# PLCArduinoV1.net
KiCad netlist of a schematic drawn in EAGLE
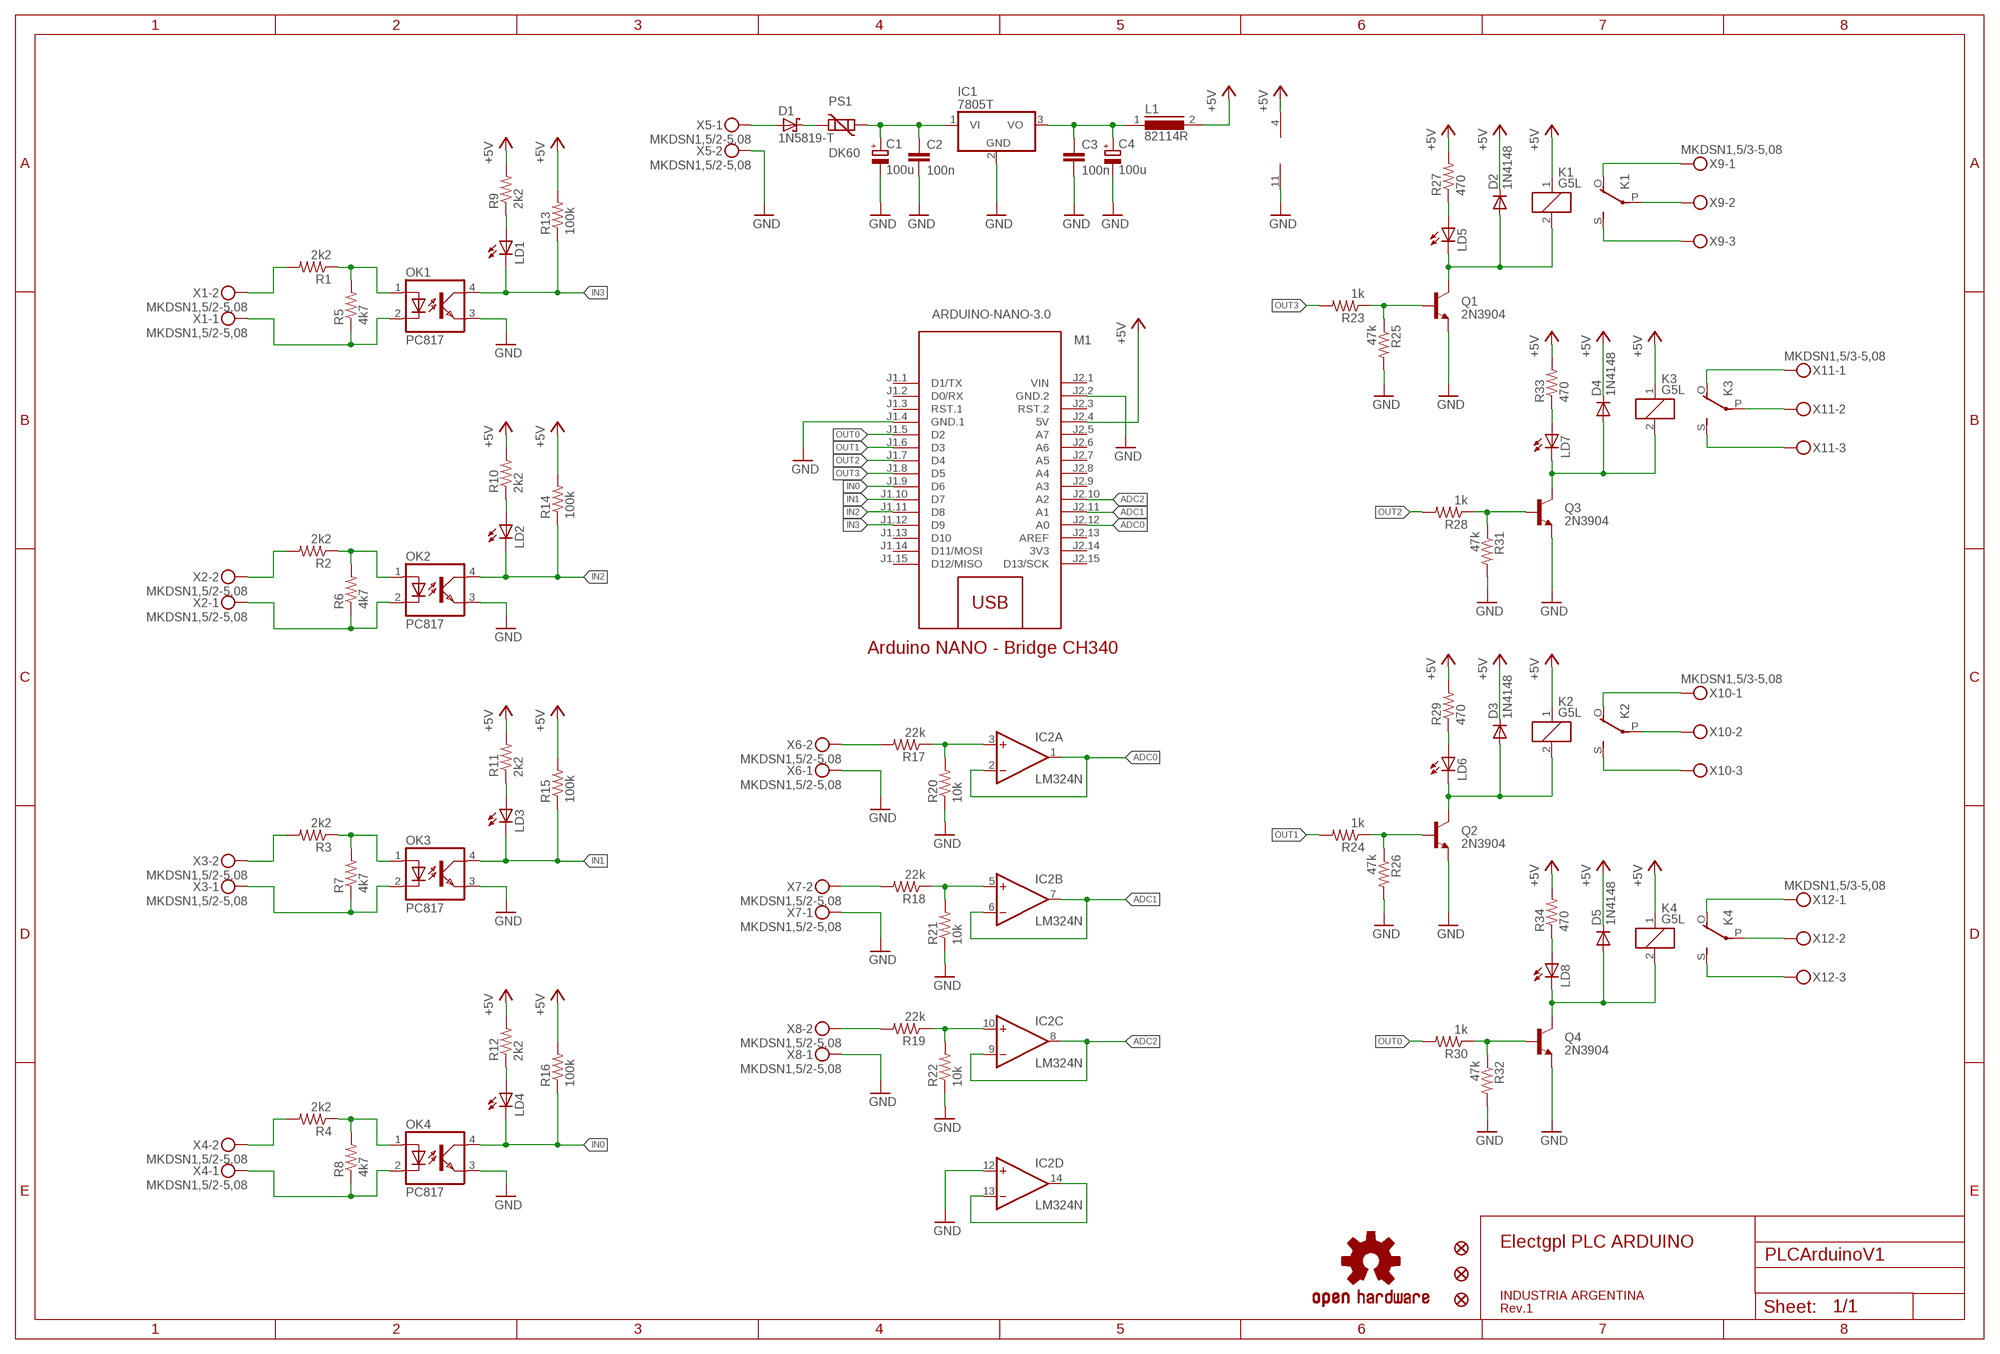
[diagram p0: schematic, sheet 1]

(export (version "E")
  (design (tool "Eeschema 10.0.6"))
  (components
    (comp (ref "C1")
      (value "100u")
      (footprint "eagle-import:E3,5-8")
      (libsource (lib "eagle-import") (part "CPOL-EUE3.5-8"))
    )
    (comp (ref "C2")
      (value "100n")
      (footprint "eagle-import:C050-024X044")
      (libsource (lib "eagle-import") (part "C-EU050-024X044"))
    )
    (comp (ref "C3")
      (value "100n")
      (footprint "eagle-import:C050-024X044")
      (libsource (lib "eagle-import") (part "C-EU050-024X044"))
    )
    (comp (ref "C4")
      (value "100u")
      (footprint "eagle-import:E3,5-8")
      (libsource (lib "eagle-import") (part "CPOL-EUE3.5-8"))
    )
    (comp (ref "D1")
      (value "1N5819-T")
      (footprint "eagle-import:DO41-7.6")
      (libsource (lib "eagle-import") (part "1N5819-T"))
    )
    (comp (ref "D2")
      (value "1N4148")
      (footprint "eagle-import:DO35-10")
      (libsource (lib "eagle-import") (part "1N4148"))
    )
    (comp (ref "D3")
      (value "1N4148")
      (footprint "eagle-import:DO35-10")
      (libsource (lib "eagle-import") (part "1N4148"))
    )
    (comp (ref "D4")
      (value "1N4148")
      (footprint "eagle-import:DO35-10")
      (libsource (lib "eagle-import") (part "1N4148"))
    )
    (comp (ref "D5")
      (value "1N4148")
      (footprint "eagle-import:DO35-10")
      (libsource (lib "eagle-import") (part "1N4148"))
    )
    (comp (ref "IC1")
      (value "7805T")
      (footprint "eagle-import:TO220H")
      (libsource (lib "eagle-import") (part "78T05"))
    )
    (comp (ref "IC2")
      (value "LM324N")
      (footprint "eagle-import:DIL14")
      (libsource (lib "eagle-import") (part "LM324N"))
    )
    (comp (ref "JP1")
      (value "FIDUCIAL1X2.5")
      (footprint "eagle-import:FIDUCIAL-1X2.5")
      (libsource (lib "eagle-import") (part "FIDUCIAL1X2.5"))
    )
    (comp (ref "JP2")
      (value "FIDUCIAL1X2.5")
      (footprint "eagle-import:FIDUCIAL-1X2.5")
      (libsource (lib "eagle-import") (part "FIDUCIAL1X2.5"))
    )
    (comp (ref "JP3")
      (value "FIDUCIAL1X2.5")
      (footprint "eagle-import:FIDUCIAL-1X2.5")
      (libsource (lib "eagle-import") (part "FIDUCIAL1X2.5"))
    )
    (comp (ref "K1")
      (value "G5L")
      (footprint "eagle-import:G5LE")
      (libsource (lib "eagle-import") (part "G5L"))
    )
    (comp (ref "K2")
      (value "G5L")
      (footprint "eagle-import:G5LE")
      (libsource (lib "eagle-import") (part "G5L"))
    )
    (comp (ref "K3")
      (value "G5L")
      (footprint "eagle-import:G5LE")
      (libsource (lib "eagle-import") (part "G5L"))
    )
    (comp (ref "K4")
      (value "G5L")
      (footprint "eagle-import:G5LE")
      (libsource (lib "eagle-import") (part "G5L"))
    )
    (comp (ref "L1")
      (value "82114R")
      (footprint "eagle-import:82114R")
      (libsource (lib "eagle-import") (part "82114R"))
    )
    (comp (ref "LD1")
      (value "LED3MM")
      (footprint "eagle-import:LED3MM")
      (libsource (lib "eagle-import") (part "LED3MM"))
    )
    (comp (ref "LD2")
      (value "LED3MM")
      (footprint "eagle-import:LED3MM")
      (libsource (lib "eagle-import") (part "LED3MM"))
    )
    (comp (ref "LD3")
      (value "LED3MM")
      (footprint "eagle-import:LED3MM")
      (libsource (lib "eagle-import") (part "LED3MM"))
    )
    (comp (ref "LD4")
      (value "LED3MM")
      (footprint "eagle-import:LED3MM")
      (libsource (lib "eagle-import") (part "LED3MM"))
    )
    (comp (ref "LD5")
      (value "LED3MM")
      (footprint "eagle-import:LED3MM")
      (libsource (lib "eagle-import") (part "LED3MM"))
    )
    (comp (ref "LD6")
      (value "LED3MM")
      (footprint "eagle-import:LED3MM")
      (libsource (lib "eagle-import") (part "LED3MM"))
    )
    (comp (ref "LD7")
      (value "LED3MM")
      (footprint "eagle-import:LED3MM")
      (libsource (lib "eagle-import") (part "LED3MM"))
    )
    (comp (ref "LD8")
      (value "LED3MM")
      (footprint "eagle-import:LED3MM")
      (libsource (lib "eagle-import") (part "LED3MM"))
    )
    (comp (ref "M1")
      (value "ARDUINO-NANO-3.0")
      (footprint "eagle-import:ARDUINO-NANO-3.0")
      (libsource (lib "eagle-import") (part "ARDUINO-NANO-3.0"))
    )
    (comp (ref "OK1")
      (value "PC817")
      (footprint "eagle-import:DIL04")
      (libsource (lib "eagle-import") (part "PC817"))
    )
    (comp (ref "OK2")
      (value "PC817")
      (footprint "eagle-import:DIL04")
      (libsource (lib "eagle-import") (part "PC817"))
    )
    (comp (ref "OK3")
      (value "PC817")
      (footprint "eagle-import:DIL04")
      (libsource (lib "eagle-import") (part "PC817"))
    )
    (comp (ref "OK4")
      (value "PC817")
      (footprint "eagle-import:DIL04")
      (libsource (lib "eagle-import") (part "PC817"))
    )
    (comp (ref "PS1")
      (value "DK60")
      (footprint "eagle-import:SO5K11")
      (libsource (lib "eagle-import") (part "POLYSWITCH5MM"))
    )
    (comp (ref "Q1")
      (value "2N3904")
      (footprint "eagle-import:TO92")
      (libsource (lib "eagle-import") (part "2N3904"))
    )
    (comp (ref "Q2")
      (value "2N3904")
      (footprint "eagle-import:TO92")
      (libsource (lib "eagle-import") (part "2N3904"))
    )
    (comp (ref "Q3")
      (value "2N3904")
      (footprint "eagle-import:TO92")
      (libsource (lib "eagle-import") (part "2N3904"))
    )
    (comp (ref "Q4")
      (value "2N3904")
      (footprint "eagle-import:TO92")
      (libsource (lib "eagle-import") (part "2N3904"))
    )
    (comp (ref "R1")
      (value "2k2")
      (footprint "eagle-import:0204_5")
      (libsource (lib "eagle-import") (part "R-US_0204/5"))
    )
    (comp (ref "R2")
      (value "2k2")
      (footprint "eagle-import:0204_5")
      (libsource (lib "eagle-import") (part "R-US_0204/5"))
    )
    (comp (ref "R3")
      (value "2k2")
      (footprint "eagle-import:0204_5")
      (libsource (lib "eagle-import") (part "R-US_0204/5"))
    )
    (comp (ref "R4")
      (value "2k2")
      (footprint "eagle-import:0204_5")
      (libsource (lib "eagle-import") (part "R-US_0204/5"))
    )
    (comp (ref "R5")
      (value "4k7")
      (footprint "eagle-import:0204_5")
      (libsource (lib "eagle-import") (part "R-US_0204/5"))
    )
    (comp (ref "R6")
      (value "4k7")
      (footprint "eagle-import:0204_5")
      (libsource (lib "eagle-import") (part "R-US_0204/5"))
    )
    (comp (ref "R7")
      (value "4k7")
      (footprint "eagle-import:0204_5")
      (libsource (lib "eagle-import") (part "R-US_0204/5"))
    )
    (comp (ref "R8")
      (value "4k7")
      (footprint "eagle-import:0204_5")
      (libsource (lib "eagle-import") (part "R-US_0204/5"))
    )
    (comp (ref "R9")
      (value "2k2")
      (footprint "eagle-import:0204_5")
      (libsource (lib "eagle-import") (part "R-US_0204/5"))
    )
    (comp (ref "R10")
      (value "2k2")
      (footprint "eagle-import:0204_5")
      (libsource (lib "eagle-import") (part "R-US_0204/5"))
    )
    (comp (ref "R11")
      (value "2k2")
      (footprint "eagle-import:0204_5")
      (libsource (lib "eagle-import") (part "R-US_0204/5"))
    )
    (comp (ref "R12")
      (value "2k2")
      (footprint "eagle-import:0204_5")
      (libsource (lib "eagle-import") (part "R-US_0204/5"))
    )
    (comp (ref "R13")
      (value "100k")
      (footprint "eagle-import:0204_5")
      (libsource (lib "eagle-import") (part "R-US_0204/5"))
    )
    (comp (ref "R14")
      (value "100k")
      (footprint "eagle-import:0204_5")
      (libsource (lib "eagle-import") (part "R-US_0204/5"))
    )
    (comp (ref "R15")
      (value "100k")
      (footprint "eagle-import:0204_5")
      (libsource (lib "eagle-import") (part "R-US_0204/5"))
    )
    (comp (ref "R16")
      (value "100k")
      (footprint "eagle-import:0204_5")
      (libsource (lib "eagle-import") (part "R-US_0204/5"))
    )
    (comp (ref "R17")
      (value "22k")
      (footprint "eagle-import:0204_5")
      (libsource (lib "eagle-import") (part "R-US_0204/5"))
    )
    (comp (ref "R18")
      (value "22k")
      (footprint "eagle-import:0204_5")
      (libsource (lib "eagle-import") (part "R-US_0204/5"))
    )
    (comp (ref "R19")
      (value "22k")
      (footprint "eagle-import:0204_5")
      (libsource (lib "eagle-import") (part "R-US_0204/5"))
    )
    (comp (ref "R20")
      (value "10k")
      (footprint "eagle-import:0204_5")
      (libsource (lib "eagle-import") (part "R-US_0204/5"))
    )
    (comp (ref "R21")
      (value "10k")
      (footprint "eagle-import:0204_5")
      (libsource (lib "eagle-import") (part "R-US_0204/5"))
    )
    (comp (ref "R22")
      (value "10k")
      (footprint "eagle-import:0204_5")
      (libsource (lib "eagle-import") (part "R-US_0204/5"))
    )
    (comp (ref "R23")
      (value "1k")
      (footprint "eagle-import:0204_5")
      (libsource (lib "eagle-import") (part "R-US_0204/5"))
    )
    (comp (ref "R24")
      (value "1k")
      (footprint "eagle-import:0204_5")
      (libsource (lib "eagle-import") (part "R-US_0204/5"))
    )
    (comp (ref "R25")
      (value "47k")
      (footprint "eagle-import:0204_5")
      (libsource (lib "eagle-import") (part "R-US_0204/5"))
    )
    (comp (ref "R26")
      (value "47k")
      (footprint "eagle-import:0204_5")
      (libsource (lib "eagle-import") (part "R-US_0204/5"))
    )
    (comp (ref "R27")
      (value "470")
      (footprint "eagle-import:0204_5")
      (libsource (lib "eagle-import") (part "R-US_0204/5"))
    )
    (comp (ref "R28")
      (value "1k")
      (footprint "eagle-import:0204_5")
      (libsource (lib "eagle-import") (part "R-US_0204/5"))
    )
    (comp (ref "R29")
      (value "470")
      (footprint "eagle-import:0204_5")
      (libsource (lib "eagle-import") (part "R-US_0204/5"))
    )
    (comp (ref "R30")
      (value "1k")
      (footprint "eagle-import:0204_5")
      (libsource (lib "eagle-import") (part "R-US_0204/5"))
    )
    (comp (ref "R31")
      (value "47k")
      (footprint "eagle-import:0204_5")
      (libsource (lib "eagle-import") (part "R-US_0204/5"))
    )
    (comp (ref "R32")
      (value "47k")
      (footprint "eagle-import:0204_5")
      (libsource (lib "eagle-import") (part "R-US_0204/5"))
    )
    (comp (ref "R33")
      (value "470")
      (footprint "eagle-import:0204_5")
      (libsource (lib "eagle-import") (part "R-US_0204/5"))
    )
    (comp (ref "R34")
      (value "470")
      (footprint "eagle-import:0204_5")
      (libsource (lib "eagle-import") (part "R-US_0204/5"))
    )
    (comp (ref "U1")
      (value "OSHW-LOGOM")
      (footprint "eagle-import:OSHW-LOGO-M")
      (libsource (lib "eagle-import") (part "OSHW-LOGOM"))
    )
    (comp (ref "X1")
      (value "MKDSN1,5/2-5,08")
      (footprint "eagle-import:MKDSN1,5_2-5,08")
      (libsource (lib "eagle-import") (part "MKDSN1,5/2-5,08"))
    )
    (comp (ref "X2")
      (value "MKDSN1,5/2-5,08")
      (footprint "eagle-import:MKDSN1,5_2-5,08")
      (libsource (lib "eagle-import") (part "MKDSN1,5/2-5,08"))
    )
    (comp (ref "X3")
      (value "MKDSN1,5/2-5,08")
      (footprint "eagle-import:MKDSN1,5_2-5,08")
      (libsource (lib "eagle-import") (part "MKDSN1,5/2-5,08"))
    )
    (comp (ref "X4")
      (value "MKDSN1,5/2-5,08")
      (footprint "eagle-import:MKDSN1,5_2-5,08")
      (libsource (lib "eagle-import") (part "MKDSN1,5/2-5,08"))
    )
    (comp (ref "X5")
      (value "MKDSN1,5/2-5,08")
      (footprint "eagle-import:MKDSN1,5_2-5,08")
      (libsource (lib "eagle-import") (part "MKDSN1,5/2-5,08"))
    )
    (comp (ref "X6")
      (value "MKDSN1,5/2-5,08")
      (footprint "eagle-import:MKDSN1,5_2-5,08")
      (libsource (lib "eagle-import") (part "MKDSN1,5/2-5,08"))
    )
    (comp (ref "X7")
      (value "MKDSN1,5/2-5,08")
      (footprint "eagle-import:MKDSN1,5_2-5,08")
      (libsource (lib "eagle-import") (part "MKDSN1,5/2-5,08"))
    )
    (comp (ref "X8")
      (value "MKDSN1,5/2-5,08")
      (footprint "eagle-import:MKDSN1,5_2-5,08")
      (libsource (lib "eagle-import") (part "MKDSN1,5/2-5,08"))
    )
    (comp (ref "X9")
      (value "MKDSN1,5/3-5,08")
      (footprint "eagle-import:MKDSN1,5_3-5,08")
      (libsource (lib "eagle-import") (part "MKDSN1,5/3-5,08"))
    )
    (comp (ref "X10")
      (value "MKDSN1,5/3-5,08")
      (footprint "eagle-import:MKDSN1,5_3-5,08")
      (libsource (lib "eagle-import") (part "MKDSN1,5/3-5,08"))
    )
    (comp (ref "X11")
      (value "MKDSN1,5/3-5,08")
      (footprint "eagle-import:MKDSN1,5_3-5,08")
      (libsource (lib "eagle-import") (part "MKDSN1,5/3-5,08"))
    )
    (comp (ref "X12")
      (value "MKDSN1,5/3-5,08")
      (footprint "eagle-import:MKDSN1,5_3-5,08")
      (libsource (lib "eagle-import") (part "MKDSN1,5/3-5,08"))
    )
  )
  (nets
    (net (code "1") (name "+5V") (class "Default")
      (node (ref "D2") (pin "C") (pinfunction "C_C") (pintype "passive"))
      (node (ref "D3") (pin "C") (pinfunction "C_C") (pintype "passive"))
      (node (ref "D4") (pin "C") (pinfunction "C_C") (pintype "passive"))
      (node (ref "D5") (pin "C") (pinfunction "C_C") (pintype "passive"))
      (node (ref "IC2") (pin "4") (pinfunction "V+_4") (pintype "power_in"))
      (node (ref "K1") (pin "1") (pinfunction "1_1") (pintype "passive"))
      (node (ref "K2") (pin "1") (pinfunction "1_1") (pintype "passive"))
      (node (ref "K3") (pin "1") (pinfunction "1_1") (pintype "passive"))
      (node (ref "K4") (pin "1") (pinfunction "1_1") (pintype "passive"))
      (node (ref "L1") (pin "2") (pinfunction "2_2") (pintype "passive"))
      (node (ref "M1") (pin "J2.4") (pinfunction "5V_J2.4") (pintype "power_in"))
      (node (ref "R10") (pin "2") (pinfunction "2_2") (pintype "passive"))
      (node (ref "R11") (pin "2") (pinfunction "2_2") (pintype "passive"))
      (node (ref "R12") (pin "2") (pinfunction "2_2") (pintype "passive"))
      (node (ref "R13") (pin "2") (pinfunction "2_2") (pintype "passive"))
      (node (ref "R14") (pin "2") (pinfunction "2_2") (pintype "passive"))
      (node (ref "R15") (pin "2") (pinfunction "2_2") (pintype "passive"))
      (node (ref "R16") (pin "2") (pinfunction "2_2") (pintype "passive"))
      (node (ref "R27") (pin "2") (pinfunction "2_2") (pintype "passive"))
      (node (ref "R29") (pin "2") (pinfunction "2_2") (pintype "passive"))
      (node (ref "R33") (pin "2") (pinfunction "2_2") (pintype "passive"))
      (node (ref "R34") (pin "2") (pinfunction "2_2") (pintype "passive"))
      (node (ref "R9") (pin "2") (pinfunction "2_2") (pintype "passive"))
    )
    (net (code "2") (name "/3V3") (class "Default")
      (node (ref "M1") (pin "J2.14") (pinfunction "3V3_J2.14") (pintype "power_in"))
    )
    (net (code "3") (name "/VIN") (class "Default")
      (node (ref "M1") (pin "J2.1") (pinfunction "VIN_J2.1") (pintype "power_in"))
    )
    (net (code "4") (name "ADC0") (class "Default")
      (node (ref "IC2") (pin "1") (pinfunction "OUT_1") (pintype "output"))
      (node (ref "IC2") (pin "2") (pinfunction "-IN_2") (pintype "input"))
      (node (ref "M1") (pin "J2.12") (pinfunction "A0_J2.12") (pintype "bidirectional"))
    )
    (net (code "5") (name "ADC1") (class "Default")
      (node (ref "IC2") (pin "6") (pinfunction "-IN_6") (pintype "input"))
      (node (ref "IC2") (pin "7") (pinfunction "OUT_7") (pintype "output"))
      (node (ref "M1") (pin "J2.11") (pinfunction "A1_J2.11") (pintype "bidirectional"))
    )
    (net (code "6") (name "ADC2") (class "Default")
      (node (ref "IC2") (pin "8") (pinfunction "OUT_8") (pintype "output"))
      (node (ref "IC2") (pin "9") (pinfunction "-IN_9") (pintype "input"))
      (node (ref "M1") (pin "J2.10") (pinfunction "A2_J2.10") (pintype "bidirectional"))
    )
    (net (code "7") (name "GND") (class "Default")
      (node (ref "C1") (pin "-") (pinfunction "-_-") (pintype "passive"))
      (node (ref "C2") (pin "2") (pinfunction "2_2") (pintype "passive"))
      (node (ref "C3") (pin "2") (pinfunction "2_2") (pintype "passive"))
      (node (ref "C4") (pin "-") (pinfunction "-_-") (pintype "passive"))
      (node (ref "IC1") (pin "2") (pinfunction "GND_2") (pintype "passive"))
      (node (ref "IC2") (pin "11") (pinfunction "V-_11") (pintype "power_in"))
      (node (ref "IC2") (pin "12") (pinfunction "+IN_12") (pintype "input"))
      (node (ref "M1") (pin "J1.4") (pinfunction "GND.1_J1.4") (pintype "power_in"))
      (node (ref "M1") (pin "J2.2") (pinfunction "GND.2_J2.2") (pintype "power_in"))
      (node (ref "OK1") (pin "3") (pinfunction "EMIT_3") (pintype "passive"))
      (node (ref "OK2") (pin "3") (pinfunction "EMIT_3") (pintype "passive"))
      (node (ref "OK3") (pin "3") (pinfunction "EMIT_3") (pintype "passive"))
      (node (ref "OK4") (pin "3") (pinfunction "EMIT_3") (pintype "passive"))
      (node (ref "Q1") (pin "3") (pinfunction "E_3") (pintype "passive"))
      (node (ref "Q2") (pin "3") (pinfunction "E_3") (pintype "passive"))
      (node (ref "Q3") (pin "3") (pinfunction "E_3") (pintype "passive"))
      (node (ref "Q4") (pin "3") (pinfunction "E_3") (pintype "passive"))
      (node (ref "R20") (pin "1") (pinfunction "1_1") (pintype "passive"))
      (node (ref "R21") (pin "1") (pinfunction "1_1") (pintype "passive"))
      (node (ref "R22") (pin "1") (pinfunction "1_1") (pintype "passive"))
      (node (ref "R25") (pin "2") (pinfunction "2_2") (pintype "passive"))
      (node (ref "R26") (pin "2") (pinfunction "2_2") (pintype "passive"))
      (node (ref "R31") (pin "2") (pinfunction "2_2") (pintype "passive"))
      (node (ref "R32") (pin "2") (pinfunction "2_2") (pintype "passive"))
      (node (ref "X5") (pin "2") (pinfunction "KL_2") (pintype "passive"))
      (node (ref "X6") (pin "1") (pinfunction "KL_1") (pintype "passive"))
      (node (ref "X7") (pin "1") (pinfunction "KL_1") (pintype "passive"))
      (node (ref "X8") (pin "1") (pinfunction "KL_1") (pintype "passive"))
    )
    (net (code "8") (name "IN0") (class "Default")
      (node (ref "LD4") (pin "K") (pinfunction "C_K") (pintype "passive"))
      (node (ref "M1") (pin "J1.9") (pinfunction "D6_J1.9") (pintype "bidirectional"))
      (node (ref "OK4") (pin "4") (pinfunction "COL_4") (pintype "passive"))
      (node (ref "R16") (pin "1") (pinfunction "1_1") (pintype "passive"))
    )
    (net (code "9") (name "IN1") (class "Default")
      (node (ref "LD3") (pin "K") (pinfunction "C_K") (pintype "passive"))
      (node (ref "M1") (pin "J1.10") (pinfunction "D7_J1.10") (pintype "bidirectional"))
      (node (ref "OK3") (pin "4") (pinfunction "COL_4") (pintype "passive"))
      (node (ref "R15") (pin "1") (pinfunction "1_1") (pintype "passive"))
    )
    (net (code "10") (name "IN2") (class "Default")
      (node (ref "LD2") (pin "K") (pinfunction "C_K") (pintype "passive"))
      (node (ref "M1") (pin "J1.11") (pinfunction "D8_J1.11") (pintype "bidirectional"))
      (node (ref "OK2") (pin "4") (pinfunction "COL_4") (pintype "passive"))
      (node (ref "R14") (pin "1") (pinfunction "1_1") (pintype "passive"))
    )
    (net (code "11") (name "IN3") (class "Default")
      (node (ref "LD1") (pin "K") (pinfunction "C_K") (pintype "passive"))
      (node (ref "M1") (pin "J1.12") (pinfunction "D9_J1.12") (pintype "bidirectional"))
      (node (ref "OK1") (pin "4") (pinfunction "COL_4") (pintype "passive"))
      (node (ref "R13") (pin "1") (pinfunction "1_1") (pintype "passive"))
    )
    (net (code "12") (name "Net-(D1-PadC)") (class "Default")
      (node (ref "D1") (pin "C") (pinfunction "C_C") (pintype "passive"))
      (node (ref "PS1") (pin "2") (pinfunction "2_2") (pintype "passive"))
    )
    (net (code "13") (name "Net-(IC1-VI)") (class "Default")
      (node (ref "C1") (pin "+") (pinfunction "+_+") (pintype "passive"))
      (node (ref "C2") (pin "1") (pinfunction "1_1") (pintype "passive"))
      (node (ref "IC1") (pin "1") (pinfunction "VI_1") (pintype "input"))
      (node (ref "PS1") (pin "1") (pinfunction "1_1") (pintype "passive"))
    )
    (net (code "14") (name "Net-(IC1-VO)") (class "Default")
      (node (ref "C3") (pin "1") (pinfunction "1_1") (pintype "passive"))
      (node (ref "C4") (pin "+") (pinfunction "+_+") (pintype "passive"))
      (node (ref "IC1") (pin "3") (pinfunction "VO_3") (pintype "passive"))
      (node (ref "L1") (pin "1") (pinfunction "1_1") (pintype "passive"))
    )
    (net (code "15") (name "Net-(IC2A-+IN)") (class "Default")
      (node (ref "IC2") (pin "3") (pinfunction "+IN_3") (pintype "input"))
      (node (ref "R17") (pin "1") (pinfunction "1_1") (pintype "passive"))
      (node (ref "R20") (pin "2") (pinfunction "2_2") (pintype "passive"))
    )
    (net (code "16") (name "Net-(IC2B-+IN)") (class "Default")
      (node (ref "IC2") (pin "5") (pinfunction "+IN_5") (pintype "input"))
      (node (ref "R18") (pin "1") (pinfunction "1_1") (pintype "passive"))
      (node (ref "R21") (pin "2") (pinfunction "2_2") (pintype "passive"))
    )
    (net (code "17") (name "Net-(IC2C-+IN)") (class "Default")
      (node (ref "IC2") (pin "10") (pinfunction "+IN_10") (pintype "input"))
      (node (ref "R19") (pin "1") (pinfunction "1_1") (pintype "passive"))
      (node (ref "R22") (pin "2") (pinfunction "2_2") (pintype "passive"))
    )
    (net (code "18") (name "Net-(IC2D--IN)") (class "Default")
      (node (ref "IC2") (pin "13") (pinfunction "-IN_13") (pintype "input"))
      (node (ref "IC2") (pin "14") (pinfunction "OUT_14") (pintype "output"))
    )
    (net (code "19") (name "Net-(LD1-PadA)") (class "Default")
      (node (ref "LD1") (pin "A") (pinfunction "A_A") (pintype "passive"))
      (node (ref "R9") (pin "1") (pinfunction "1_1") (pintype "passive"))
    )
    (net (code "20") (name "Net-(LD2-PadA)") (class "Default")
      (node (ref "LD2") (pin "A") (pinfunction "A_A") (pintype "passive"))
      (node (ref "R10") (pin "1") (pinfunction "1_1") (pintype "passive"))
    )
    (net (code "21") (name "Net-(LD3-PadA)") (class "Default")
      (node (ref "LD3") (pin "A") (pinfunction "A_A") (pintype "passive"))
      (node (ref "R11") (pin "1") (pinfunction "1_1") (pintype "passive"))
    )
    (net (code "22") (name "Net-(LD4-PadA)") (class "Default")
      (node (ref "LD4") (pin "A") (pinfunction "A_A") (pintype "passive"))
      (node (ref "R12") (pin "1") (pinfunction "1_1") (pintype "passive"))
    )
    (net (code "23") (name "Net-(LD5-C)") (class "Default")
      (node (ref "D2") (pin "A") (pinfunction "A_A") (pintype "passive"))
      (node (ref "K1") (pin "2") (pinfunction "2_2") (pintype "passive"))
      (node (ref "LD5") (pin "K") (pinfunction "C_K") (pintype "passive"))
      (node (ref "Q1") (pin "1") (pinfunction "C_1") (pintype "passive"))
    )
    (net (code "24") (name "Net-(LD5-PadA)") (class "Default")
      (node (ref "LD5") (pin "A") (pinfunction "A_A") (pintype "passive"))
      (node (ref "R27") (pin "1") (pinfunction "1_1") (pintype "passive"))
    )
    (net (code "25") (name "Net-(LD6-C)") (class "Default")
      (node (ref "D3") (pin "A") (pinfunction "A_A") (pintype "passive"))
      (node (ref "K2") (pin "2") (pinfunction "2_2") (pintype "passive"))
      (node (ref "LD6") (pin "K") (pinfunction "C_K") (pintype "passive"))
      (node (ref "Q2") (pin "1") (pinfunction "C_1") (pintype "passive"))
    )
    (net (code "26") (name "Net-(LD6-PadA)") (class "Default")
      (node (ref "LD6") (pin "A") (pinfunction "A_A") (pintype "passive"))
      (node (ref "R29") (pin "1") (pinfunction "1_1") (pintype "passive"))
    )
    (net (code "27") (name "Net-(LD7-C)") (class "Default")
      (node (ref "D4") (pin "A") (pinfunction "A_A") (pintype "passive"))
      (node (ref "K3") (pin "2") (pinfunction "2_2") (pintype "passive"))
      (node (ref "LD7") (pin "K") (pinfunction "C_K") (pintype "passive"))
      (node (ref "Q3") (pin "1") (pinfunction "C_1") (pintype "passive"))
    )
    (net (code "28") (name "Net-(LD7-PadA)") (class "Default")
      (node (ref "LD7") (pin "A") (pinfunction "A_A") (pintype "passive"))
      (node (ref "R33") (pin "1") (pinfunction "1_1") (pintype "passive"))
    )
    (net (code "29") (name "Net-(LD8-C)") (class "Default")
      (node (ref "D5") (pin "A") (pinfunction "A_A") (pintype "passive"))
      (node (ref "K4") (pin "2") (pinfunction "2_2") (pintype "passive"))
      (node (ref "LD8") (pin "K") (pinfunction "C_K") (pintype "passive"))
      (node (ref "Q4") (pin "1") (pinfunction "C_1") (pintype "passive"))
    )
    (net (code "30") (name "Net-(LD8-PadA)") (class "Default")
      (node (ref "LD8") (pin "A") (pinfunction "A_A") (pintype "passive"))
      (node (ref "R34") (pin "1") (pinfunction "1_1") (pintype "passive"))
    )
    (net (code "31") (name "Net-(OK1-A)") (class "Default")
      (node (ref "OK1") (pin "1") (pinfunction "A_1") (pintype "passive"))
      (node (ref "R1") (pin "1") (pinfunction "1_1") (pintype "passive"))
      (node (ref "R5") (pin "2") (pinfunction "2_2") (pintype "passive"))
    )
    (net (code "32") (name "Net-(OK1-C)") (class "Default")
      (node (ref "OK1") (pin "2") (pinfunction "C_2") (pintype "passive"))
      (node (ref "R5") (pin "1") (pinfunction "1_1") (pintype "passive"))
      (node (ref "X1") (pin "1") (pinfunction "KL_1") (pintype "passive"))
    )
    (net (code "33") (name "Net-(OK2-A)") (class "Default")
      (node (ref "OK2") (pin "1") (pinfunction "A_1") (pintype "passive"))
      (node (ref "R2") (pin "1") (pinfunction "1_1") (pintype "passive"))
      (node (ref "R6") (pin "2") (pinfunction "2_2") (pintype "passive"))
    )
    (net (code "34") (name "Net-(OK2-C)") (class "Default")
      (node (ref "OK2") (pin "2") (pinfunction "C_2") (pintype "passive"))
      (node (ref "R6") (pin "1") (pinfunction "1_1") (pintype "passive"))
      (node (ref "X2") (pin "1") (pinfunction "KL_1") (pintype "passive"))
    )
    (net (code "35") (name "Net-(OK3-A)") (class "Default")
      (node (ref "OK3") (pin "1") (pinfunction "A_1") (pintype "passive"))
      (node (ref "R3") (pin "1") (pinfunction "1_1") (pintype "passive"))
      (node (ref "R7") (pin "2") (pinfunction "2_2") (pintype "passive"))
    )
    (net (code "36") (name "Net-(OK3-C)") (class "Default")
      (node (ref "OK3") (pin "2") (pinfunction "C_2") (pintype "passive"))
      (node (ref "R7") (pin "1") (pinfunction "1_1") (pintype "passive"))
      (node (ref "X3") (pin "1") (pinfunction "KL_1") (pintype "passive"))
    )
    (net (code "37") (name "Net-(OK4-A)") (class "Default")
      (node (ref "OK4") (pin "1") (pinfunction "A_1") (pintype "passive"))
      (node (ref "R4") (pin "1") (pinfunction "1_1") (pintype "passive"))
      (node (ref "R8") (pin "2") (pinfunction "2_2") (pintype "passive"))
    )
    (net (code "38") (name "Net-(OK4-C)") (class "Default")
      (node (ref "OK4") (pin "2") (pinfunction "C_2") (pintype "passive"))
      (node (ref "R8") (pin "1") (pinfunction "1_1") (pintype "passive"))
      (node (ref "X4") (pin "1") (pinfunction "KL_1") (pintype "passive"))
    )
    (net (code "39") (name "Net-(Q1-B)") (class "Default")
      (node (ref "Q1") (pin "2") (pinfunction "B_2") (pintype "passive"))
      (node (ref "R23") (pin "1") (pinfunction "1_1") (pintype "passive"))
      (node (ref "R25") (pin "1") (pinfunction "1_1") (pintype "passive"))
    )
    (net (code "40") (name "Net-(Q2-B)") (class "Default")
      (node (ref "Q2") (pin "2") (pinfunction "B_2") (pintype "passive"))
      (node (ref "R24") (pin "1") (pinfunction "1_1") (pintype "passive"))
      (node (ref "R26") (pin "1") (pinfunction "1_1") (pintype "passive"))
    )
    (net (code "41") (name "Net-(Q3-B)") (class "Default")
      (node (ref "Q3") (pin "2") (pinfunction "B_2") (pintype "passive"))
      (node (ref "R28") (pin "1") (pinfunction "1_1") (pintype "passive"))
      (node (ref "R31") (pin "1") (pinfunction "1_1") (pintype "passive"))
    )
    (net (code "42") (name "Net-(Q4-B)") (class "Default")
      (node (ref "Q4") (pin "2") (pinfunction "B_2") (pintype "passive"))
      (node (ref "R30") (pin "1") (pinfunction "1_1") (pintype "passive"))
      (node (ref "R32") (pin "1") (pinfunction "1_1") (pintype "passive"))
    )
    (net (code "43") (name "Net-(X1B-KL)") (class "Default")
      (node (ref "R1") (pin "2") (pinfunction "2_2") (pintype "passive"))
      (node (ref "X1") (pin "2") (pinfunction "KL_2") (pintype "passive"))
    )
    (net (code "44") (name "Net-(X2B-KL)") (class "Default")
      (node (ref "R2") (pin "2") (pinfunction "2_2") (pintype "passive"))
      (node (ref "X2") (pin "2") (pinfunction "KL_2") (pintype "passive"))
    )
    (net (code "45") (name "Net-(X3B-KL)") (class "Default")
      (node (ref "R3") (pin "2") (pinfunction "2_2") (pintype "passive"))
      (node (ref "X3") (pin "2") (pinfunction "KL_2") (pintype "passive"))
    )
    (net (code "46") (name "Net-(X4B-KL)") (class "Default")
      (node (ref "R4") (pin "2") (pinfunction "2_2") (pintype "passive"))
      (node (ref "X4") (pin "2") (pinfunction "KL_2") (pintype "passive"))
    )
    (net (code "47") (name "Net-(X5A-KL)") (class "Default")
      (node (ref "D1") (pin "A") (pinfunction "A_A") (pintype "passive"))
      (node (ref "X5") (pin "1") (pinfunction "KL_1") (pintype "passive"))
    )
    (net (code "48") (name "Net-(X6B-KL)") (class "Default")
      (node (ref "R17") (pin "2") (pinfunction "2_2") (pintype "passive"))
      (node (ref "X6") (pin "2") (pinfunction "KL_2") (pintype "passive"))
    )
    (net (code "49") (name "Net-(X7B-KL)") (class "Default")
      (node (ref "R18") (pin "2") (pinfunction "2_2") (pintype "passive"))
      (node (ref "X7") (pin "2") (pinfunction "KL_2") (pintype "passive"))
    )
    (net (code "50") (name "Net-(X8B-KL)") (class "Default")
      (node (ref "R19") (pin "2") (pinfunction "2_2") (pintype "passive"))
      (node (ref "X8") (pin "2") (pinfunction "KL_2") (pintype "passive"))
    )
    (net (code "51") (name "Net-(X9A-KL)") (class "Default")
      (node (ref "K1") (pin "O") (pinfunction "O_O") (pintype "passive"))
      (node (ref "X9") (pin "1") (pinfunction "KL_1") (pintype "passive"))
    )
    (net (code "52") (name "Net-(X9B-KL)") (class "Default")
      (node (ref "K1") (pin "P") (pinfunction "P_P") (pintype "passive"))
      (node (ref "X9") (pin "2") (pinfunction "KL_2") (pintype "passive"))
    )
    (net (code "53") (name "Net-(X9C-KL)") (class "Default")
      (node (ref "K1") (pin "S") (pinfunction "S_S") (pintype "passive"))
      (node (ref "X9") (pin "3") (pinfunction "KL_3") (pintype "passive"))
    )
    (net (code "54") (name "Net-(X10A-KL)") (class "Default")
      (node (ref "K2") (pin "O") (pinfunction "O_O") (pintype "passive"))
      (node (ref "X10") (pin "1") (pinfunction "KL_1") (pintype "passive"))
    )
    (net (code "55") (name "Net-(X10B-KL)") (class "Default")
      (node (ref "K2") (pin "P") (pinfunction "P_P") (pintype "passive"))
      (node (ref "X10") (pin "2") (pinfunction "KL_2") (pintype "passive"))
    )
    (net (code "56") (name "Net-(X10C-KL)") (class "Default")
      (node (ref "K2") (pin "S") (pinfunction "S_S") (pintype "passive"))
      (node (ref "X10") (pin "3") (pinfunction "KL_3") (pintype "passive"))
    )
    (net (code "57") (name "Net-(X11A-KL)") (class "Default")
      (node (ref "K3") (pin "O") (pinfunction "O_O") (pintype "passive"))
      (node (ref "X11") (pin "1") (pinfunction "KL_1") (pintype "passive"))
    )
    (net (code "58") (name "Net-(X11B-KL)") (class "Default")
      (node (ref "K3") (pin "P") (pinfunction "P_P") (pintype "passive"))
      (node (ref "X11") (pin "2") (pinfunction "KL_2") (pintype "passive"))
    )
    (net (code "59") (name "Net-(X11C-KL)") (class "Default")
      (node (ref "K3") (pin "S") (pinfunction "S_S") (pintype "passive"))
      (node (ref "X11") (pin "3") (pinfunction "KL_3") (pintype "passive"))
    )
    (net (code "60") (name "Net-(X12A-KL)") (class "Default")
      (node (ref "K4") (pin "O") (pinfunction "O_O") (pintype "passive"))
      (node (ref "X12") (pin "1") (pinfunction "KL_1") (pintype "passive"))
    )
    (net (code "61") (name "Net-(X12B-KL)") (class "Default")
      (node (ref "K4") (pin "P") (pinfunction "P_P") (pintype "passive"))
      (node (ref "X12") (pin "2") (pinfunction "KL_2") (pintype "passive"))
    )
    (net (code "62") (name "Net-(X12C-KL)") (class "Default")
      (node (ref "K4") (pin "S") (pinfunction "S_S") (pintype "passive"))
      (node (ref "X12") (pin "3") (pinfunction "KL_3") (pintype "passive"))
    )
    (net (code "63") (name "OUT0") (class "Default")
      (node (ref "M1") (pin "J1.5") (pinfunction "D2_J1.5") (pintype "bidirectional"))
      (node (ref "R30") (pin "2") (pinfunction "2_2") (pintype "passive"))
    )
    (net (code "64") (name "OUT1") (class "Default")
      (node (ref "M1") (pin "J1.6") (pinfunction "D3_J1.6") (pintype "bidirectional"))
      (node (ref "R24") (pin "2") (pinfunction "2_2") (pintype "passive"))
    )
    (net (code "65") (name "OUT2") (class "Default")
      (node (ref "M1") (pin "J1.7") (pinfunction "D4_J1.7") (pintype "bidirectional"))
      (node (ref "R28") (pin "2") (pinfunction "2_2") (pintype "passive"))
    )
    (net (code "66") (name "OUT3") (class "Default")
      (node (ref "M1") (pin "J1.8") (pinfunction "D5_J1.8") (pintype "bidirectional"))
      (node (ref "R23") (pin "2") (pinfunction "2_2") (pintype "passive"))
    )
    (net (code "67") (name "unconnected-(M1-A3-PadJ2.9)") (class "Default")
      (node (ref "M1") (pin "J2.9") (pinfunction "A3_J2.9") (pintype "bidirectional"))
    )
    (net (code "68") (name "unconnected-(M1-A4-PadJ2.8)") (class "Default")
      (node (ref "M1") (pin "J2.8") (pinfunction "A4_J2.8") (pintype "bidirectional"))
    )
    (net (code "69") (name "unconnected-(M1-A5-PadJ2.7)") (class "Default")
      (node (ref "M1") (pin "J2.7") (pinfunction "A5_J2.7") (pintype "bidirectional"))
    )
    (net (code "70") (name "unconnected-(M1-A6-PadJ2.6)") (class "Default")
      (node (ref "M1") (pin "J2.6") (pinfunction "A6_J2.6") (pintype "bidirectional"))
    )
    (net (code "71") (name "unconnected-(M1-A7-PadJ2.5)") (class "Default")
      (node (ref "M1") (pin "J2.5") (pinfunction "A7_J2.5") (pintype "bidirectional"))
    )
    (net (code "72") (name "unconnected-(M1-AREF-PadJ2.13)") (class "Default")
      (node (ref "M1") (pin "J2.13") (pinfunction "AREF_J2.13") (pintype "bidirectional"))
    )
    (net (code "73") (name "unconnected-(M1-D0{slash}RX-PadJ1.2)") (class "Default")
      (node (ref "M1") (pin "J1.2") (pinfunction "D0/RX_J1.2") (pintype "bidirectional"))
    )
    (net (code "74") (name "unconnected-(M1-D1{slash}TX-PadJ1.1)") (class "Default")
      (node (ref "M1") (pin "J1.1") (pinfunction "D1/TX_J1.1") (pintype "bidirectional"))
    )
    (net (code "75") (name "unconnected-(M1-D10-PadJ1.13)") (class "Default")
      (node (ref "M1") (pin "J1.13") (pinfunction "D10_J1.13") (pintype "bidirectional"))
    )
    (net (code "76") (name "unconnected-(M1-D11{slash}MOSI-PadJ1.14)") (class "Default")
      (node (ref "M1") (pin "J1.14") (pinfunction "D11/MOSI_J1.14") (pintype "bidirectional"))
    )
    (net (code "77") (name "unconnected-(M1-D12{slash}MISO-PadJ1.15)") (class "Default")
      (node (ref "M1") (pin "J1.15") (pinfunction "D12/MISO_J1.15") (pintype "bidirectional"))
    )
    (net (code "78") (name "unconnected-(M1-D13{slash}SCK-PadJ2.15)") (class "Default")
      (node (ref "M1") (pin "J2.15") (pinfunction "D13/SCK_J2.15") (pintype "bidirectional"))
    )
    (net (code "79") (name "unconnected-(M1-RST.1-PadJ1.3)") (class "Default")
      (node (ref "M1") (pin "J1.3") (pinfunction "RST.1_J1.3") (pintype "bidirectional"))
    )
    (net (code "80") (name "unconnected-(M1-RST.2-PadJ2.3)") (class "Default")
      (node (ref "M1") (pin "J2.3") (pinfunction "RST.2_J2.3") (pintype "bidirectional"))
    )
  )
)
